# VM_Motor_v0t.net
KiCad netlist of a schematic drawn in EAGLE
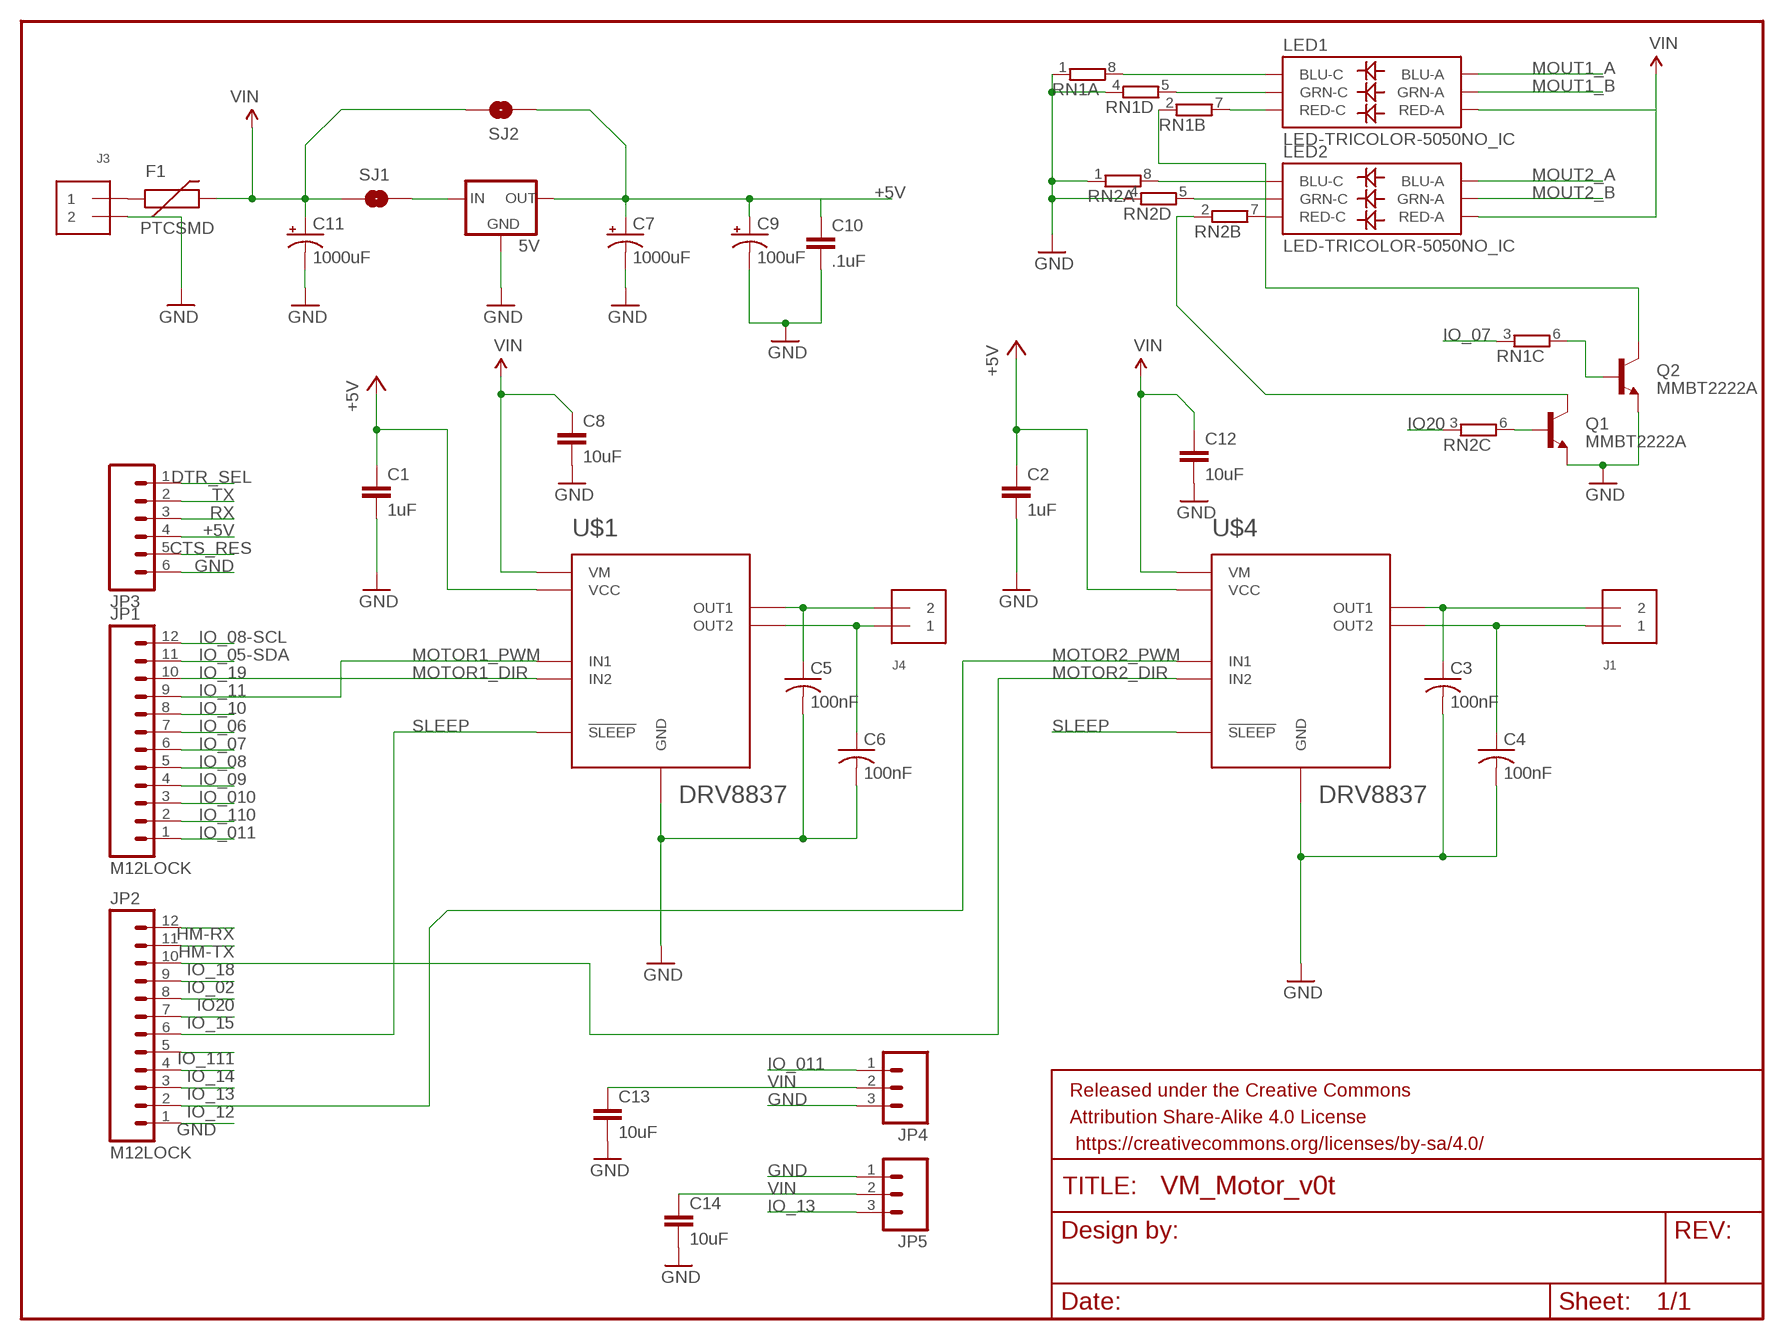
[diagram p0: schematic, sheet 1]

(export (version "E")
  (design (tool "Eeschema 10.0.6"))
  (components
    (comp (ref "5V")
      (value "V_REG_MC33269DT")
      (footprint "eagle-import:DPAK")
      (libsource (lib "eagle-import") (part "V_REG_MC33269DT"))
    )
    (comp (ref "C1")
      (value "1uF")
      (footprint "eagle-import:0402-CAP")
      (libsource (lib "eagle-import") (part "CAP0402-CAP"))
    )
    (comp (ref "C2")
      (value "1uF")
      (footprint "eagle-import:0402-CAP")
      (libsource (lib "eagle-import") (part "CAP0402-CAP"))
    )
    (comp (ref "C3")
      (value "100nF")
      (footprint "eagle-import:C0402")
      (libsource (lib "eagle-import") (part "C-USC0402"))
    )
    (comp (ref "C4")
      (value "100nF")
      (footprint "eagle-import:C0402")
      (libsource (lib "eagle-import") (part "C-USC0402"))
    )
    (comp (ref "C5")
      (value "100nF")
      (footprint "eagle-import:C0402")
      (libsource (lib "eagle-import") (part "C-USC0402"))
    )
    (comp (ref "C6")
      (value "100nF")
      (footprint "eagle-import:C0402")
      (libsource (lib "eagle-import") (part "C-USC0402"))
    )
    (comp (ref "C7")
      (value "1000uF")
      (footprint "eagle-import:140CLH-0810")
      (libsource (lib "eagle-import") (part "CPOL-US140CLH-0810"))
    )
    (comp (ref "C8")
      (value "10uF")
      (footprint "eagle-import:0402-CAP")
      (libsource (lib "eagle-import") (part "CAP0402-CAP"))
    )
    (comp (ref "C9")
      (value "100uF")
      (footprint "eagle-import:EIA3528-KIT")
      (libsource (lib "eagle-import") (part "CAP_POL3528-KIT"))
    )
    (comp (ref "C10")
      (value ".1uF")
      (footprint "eagle-import:0402-CAP")
      (libsource (lib "eagle-import") (part "CAP0402-CAP"))
    )
    (comp (ref "C11")
      (value "1000uF")
      (footprint "eagle-import:140CLH-0810")
      (libsource (lib "eagle-import") (part "CPOL-US140CLH-0810"))
    )
    (comp (ref "C12")
      (value "10uF")
      (footprint "eagle-import:0402-CAP")
      (libsource (lib "eagle-import") (part "CAP0402-CAP"))
    )
    (comp (ref "C13")
      (value "10uF")
      (footprint "eagle-import:0402-CAP")
      (libsource (lib "eagle-import") (part "CAP0402-CAP"))
    )
    (comp (ref "C14")
      (value "10uF")
      (footprint "eagle-import:0402-CAP")
      (libsource (lib "eagle-import") (part "CAP0402-CAP"))
    )
    (comp (ref "F1")
      (value "PTCSMD")
      (footprint "eagle-import:PTC-1206")
      (libsource (lib "eagle-import") (part "PTCSMD"))
    )
    (comp (ref "FRAME1")
      (value "FRAME-LETTER")
      (footprint "eagle-import:CREATIVE_COMMONS")
      (libsource (lib "eagle-import") (part "FRAME-LETTER"))
    )
    (comp (ref "J1")
      (value "TERMBLOCK_1X2")
      (footprint "eagle-import:TERMBLOCK_1X2-3.5MM")
      (libsource (lib "eagle-import") (part "TERMBLOCK_1X2"))
    )
    (comp (ref "J3")
      (value "TERMBLOCK_1X2")
      (footprint "eagle-import:TERMBLOCK_1X2-3.5MM")
      (libsource (lib "eagle-import") (part "TERMBLOCK_1X2"))
    )
    (comp (ref "J4")
      (value "TERMBLOCK_1X2")
      (footprint "eagle-import:TERMBLOCK_1X2-3.5MM")
      (libsource (lib "eagle-import") (part "TERMBLOCK_1X2"))
    )
    (comp (ref "JP1")
      (value "M12LOCK")
      (footprint "eagle-import:1X12_LOCK")
      (libsource (lib "eagle-import") (part "M12LOCK"))
    )
    (comp (ref "JP2")
      (value "M12LOCK")
      (footprint "eagle-import:1X12_LOCK")
      (libsource (lib "eagle-import") (part "M12LOCK"))
    )
    (comp (ref "JP3")
      (value "M06LOCK")
      (footprint "eagle-import:1X06_LOCK")
      (libsource (lib "eagle-import") (part "M06LOCK"))
    )
    (comp (ref "JP4")
      (value "M03LOCK")
      (footprint "eagle-import:1X03_LOCK")
      (libsource (lib "eagle-import") (part "M03LOCK"))
    )
    (comp (ref "JP5")
      (value "M03LOCK")
      (footprint "eagle-import:1X03_LOCK")
      (libsource (lib "eagle-import") (part "M03LOCK"))
    )
    (comp (ref "LED1")
      (value "LED-TRICOLOR-5050NO_IC")
      (footprint "eagle-import:LED-TRICOLOR-5050")
      (libsource (lib "eagle-import") (part "LED-TRICOLOR-5050NO_IC"))
    )
    (comp (ref "LED2")
      (value "LED-TRICOLOR-5050NO_IC")
      (footprint "eagle-import:LED-TRICOLOR-5050")
      (libsource (lib "eagle-import") (part "LED-TRICOLOR-5050NO_IC"))
    )
    (comp (ref "Q1")
      (value "MMBT2222A")
      (footprint "eagle-import:SOT23-3")
      (libsource (lib "eagle-import") (part "TRANSISTOR_NPNMMBT2222A"))
    )
    (comp (ref "Q2")
      (value "MMBT2222A")
      (footprint "eagle-import:SOT23-3")
      (libsource (lib "eagle-import") (part "TRANSISTOR_NPNMMBT2222A"))
    )
    (comp (ref "RN1")
      (value "4R-N0402ARV341")
      (footprint "eagle-import:4X0402ARV341")
      (libsource (lib "eagle-import") (part "4R-N0402ARV341"))
    )
    (comp (ref "RN2")
      (value "4R-N0402ARV341")
      (footprint "eagle-import:4X0402ARV341")
      (libsource (lib "eagle-import") (part "4R-N0402ARV341"))
    )
    (comp (ref "SJ1")
      (value "SOLDERJUMPERNO")
      (footprint "eagle-import:SJ_2S-NO")
      (libsource (lib "eagle-import") (part "SOLDERJUMPERNO"))
    )
    (comp (ref "SJ2")
      (value "SOLDERJUMPERNO")
      (footprint "eagle-import:SJ_2S-NO")
      (libsource (lib "eagle-import") (part "SOLDERJUMPERNO"))
    )
    (comp (ref "U$1")
      (value "DRV8837")
      (footprint "eagle-import:QFN8")
      (libsource (lib "eagle-import") (part "DRV8837"))
    )
    (comp (ref "U$4")
      (value "DRV8837")
      (footprint "eagle-import:QFN8")
      (libsource (lib "eagle-import") (part "DRV8837"))
    )
  )
  (nets
    (net (code "1") (name "+5V") (class "Default")
      (node (ref "5V") (pin "4") (pinfunction "OUT_4") (pintype "output"))
      (node (ref "C1") (pin "1") (pinfunction "1_1") (pintype "passive"))
      (node (ref "C10") (pin "1") (pinfunction "1_1") (pintype "passive"))
      (node (ref "C2") (pin "1") (pinfunction "1_1") (pintype "passive"))
      (node (ref "C7") (pin "+") (pinfunction "+_+") (pintype "passive"))
      (node (ref "C9") (pin "A") (pinfunction "+_A") (pintype "passive"))
      (node (ref "JP3") (pin "4") (pinfunction "4_4") (pintype "passive"))
      (node (ref "SJ2") (pin "1") (pinfunction "1_1") (pintype "passive"))
      (node (ref "U$1") (pin "P$8") (pinfunction "VCC_P$8") (pintype "bidirectional"))
      (node (ref "U$4") (pin "P$8") (pinfunction "VCC_P$8") (pintype "bidirectional"))
    )
    (net (code "2") (name "/CTS_RES") (class "Default")
      (node (ref "JP3") (pin "5") (pinfunction "5_5") (pintype "passive"))
    )
    (net (code "3") (name "/DTR_SEL") (class "Default")
      (node (ref "JP3") (pin "1") (pinfunction "1_1") (pintype "passive"))
    )
    (net (code "4") (name "/HM-RX") (class "Default")
      (node (ref "JP2") (pin "12") (pinfunction "12_12") (pintype "passive"))
    )
    (net (code "5") (name "/HM-TX") (class "Default")
      (node (ref "JP2") (pin "11") (pinfunction "11_11") (pintype "passive"))
    )
    (net (code "6") (name "/IO20") (class "Default")
      (node (ref "JP2") (pin "8") (pinfunction "8_8") (pintype "passive"))
      (node (ref "RN2") (pin "3") (pinfunction "1_3") (pintype "passive"))
    )
    (net (code "7") (name "/IO_02") (class "Default")
      (node (ref "JP2") (pin "9") (pinfunction "9_9") (pintype "passive"))
    )
    (net (code "8") (name "/IO_05-SDA") (class "Default")
      (node (ref "JP1") (pin "11") (pinfunction "11_11") (pintype "passive"))
    )
    (net (code "9") (name "/IO_06") (class "Default")
      (node (ref "JP1") (pin "7") (pinfunction "7_7") (pintype "passive"))
    )
    (net (code "10") (name "/IO_07") (class "Default")
      (node (ref "JP1") (pin "6") (pinfunction "6_6") (pintype "passive"))
      (node (ref "RN1") (pin "3") (pinfunction "1_3") (pintype "passive"))
    )
    (net (code "11") (name "/IO_08") (class "Default")
      (node (ref "JP1") (pin "5") (pinfunction "5_5") (pintype "passive"))
    )
    (net (code "12") (name "/IO_08-SCL") (class "Default")
      (node (ref "JP1") (pin "12") (pinfunction "12_12") (pintype "passive"))
    )
    (net (code "13") (name "/IO_09") (class "Default")
      (node (ref "JP1") (pin "4") (pinfunction "4_4") (pintype "passive"))
    )
    (net (code "14") (name "/IO_10") (class "Default")
      (node (ref "JP1") (pin "8") (pinfunction "8_8") (pintype "passive"))
    )
    (net (code "15") (name "/IO_010") (class "Default")
      (node (ref "JP1") (pin "3") (pinfunction "3_3") (pintype "passive"))
    )
    (net (code "16") (name "/IO_011") (class "Default")
      (node (ref "JP1") (pin "1") (pinfunction "1_1") (pintype "passive"))
      (node (ref "JP4") (pin "1") (pinfunction "1_1") (pintype "passive"))
    )
    (net (code "17") (name "/IO_13") (class "Default")
      (node (ref "JP2") (pin "3") (pinfunction "3_3") (pintype "passive"))
      (node (ref "JP5") (pin "3") (pinfunction "3_3") (pintype "passive"))
    )
    (net (code "18") (name "/IO_14") (class "Default")
      (node (ref "JP2") (pin "4") (pinfunction "4_4") (pintype "passive"))
    )
    (net (code "19") (name "/IO_15") (class "Default")
      (node (ref "JP2") (pin "7") (pinfunction "7_7") (pintype "passive"))
    )
    (net (code "20") (name "/IO_110") (class "Default")
      (node (ref "JP1") (pin "2") (pinfunction "2_2") (pintype "passive"))
    )
    (net (code "21") (name "/IO_111") (class "Default")
      (node (ref "JP2") (pin "5") (pinfunction "5_5") (pintype "passive"))
    )
    (net (code "22") (name "/MOTOR1_DIR") (class "Default")
      (node (ref "JP1") (pin "10") (pinfunction "10_10") (pintype "passive"))
      (node (ref "U$1") (pin "P$5") (pinfunction "IN2_P$5") (pintype "bidirectional"))
    )
    (net (code "23") (name "/MOTOR1_PWM") (class "Default")
      (node (ref "JP1") (pin "9") (pinfunction "9_9") (pintype "passive"))
      (node (ref "U$1") (pin "P$6") (pinfunction "IN1_P$6") (pintype "bidirectional"))
    )
    (net (code "24") (name "/MOTOR2_DIR") (class "Default")
      (node (ref "JP2") (pin "10") (pinfunction "10_10") (pintype "passive"))
      (node (ref "U$4") (pin "P$5") (pinfunction "IN2_P$5") (pintype "bidirectional"))
    )
    (net (code "25") (name "/MOTOR2_PWM") (class "Default")
      (node (ref "JP2") (pin "2") (pinfunction "2_2") (pintype "passive"))
      (node (ref "U$4") (pin "P$6") (pinfunction "IN1_P$6") (pintype "bidirectional"))
    )
    (net (code "26") (name "/MOUT1_A") (class "Default")
      (node (ref "C5") (pin "1") (pinfunction "1_1") (pintype "passive"))
      (node (ref "J4") (pin "2") (pinfunction "2_2") (pintype "passive"))
      (node (ref "LED1") (pin "3") (pinfunction "BLU-A_3") (pintype "bidirectional"))
      (node (ref "U$1") (pin "P$2") (pinfunction "OUT1_P$2") (pintype "bidirectional"))
    )
    (net (code "27") (name "/MOUT1_B") (class "Default")
      (node (ref "C6") (pin "1") (pinfunction "1_1") (pintype "passive"))
      (node (ref "J4") (pin "1") (pinfunction "1_1") (pintype "passive"))
      (node (ref "LED1") (pin "1") (pinfunction "GRN-A_1") (pintype "bidirectional"))
      (node (ref "U$1") (pin "P$3") (pinfunction "OUT2_P$3") (pintype "bidirectional"))
    )
    (net (code "28") (name "/MOUT2_A") (class "Default")
      (node (ref "C3") (pin "1") (pinfunction "1_1") (pintype "passive"))
      (node (ref "J1") (pin "2") (pinfunction "2_2") (pintype "passive"))
      (node (ref "LED2") (pin "3") (pinfunction "BLU-A_3") (pintype "bidirectional"))
      (node (ref "U$4") (pin "P$2") (pinfunction "OUT1_P$2") (pintype "bidirectional"))
    )
    (net (code "29") (name "/MOUT2_B") (class "Default")
      (node (ref "C4") (pin "1") (pinfunction "1_1") (pintype "passive"))
      (node (ref "J1") (pin "1") (pinfunction "1_1") (pintype "passive"))
      (node (ref "LED2") (pin "1") (pinfunction "GRN-A_1") (pintype "bidirectional"))
      (node (ref "U$4") (pin "P$3") (pinfunction "OUT2_P$3") (pintype "bidirectional"))
    )
    (net (code "30") (name "/RX") (class "Default")
      (node (ref "JP3") (pin "3") (pinfunction "3_3") (pintype "passive"))
    )
    (net (code "31") (name "/SLEEP") (class "Default")
      (node (ref "JP2") (pin "6") (pinfunction "6_6") (pintype "passive"))
      (node (ref "U$1") (pin "P$7") (pinfunction "~{SLEEP}_P$7") (pintype "bidirectional"))
      (node (ref "U$4") (pin "P$7") (pinfunction "~{SLEEP}_P$7") (pintype "bidirectional"))
    )
    (net (code "32") (name "/TX") (class "Default")
      (node (ref "JP3") (pin "2") (pinfunction "2_2") (pintype "passive"))
    )
    (net (code "33") (name "GND") (class "Default")
      (node (ref "5V") (pin "1") (pinfunction "GND_1") (pintype "input"))
      (node (ref "C1") (pin "2") (pinfunction "2_2") (pintype "passive"))
      (node (ref "C10") (pin "2") (pinfunction "2_2") (pintype "passive"))
      (node (ref "C11") (pin "-") (pinfunction "-_-") (pintype "passive"))
      (node (ref "C12") (pin "2") (pinfunction "2_2") (pintype "passive"))
      (node (ref "C13") (pin "2") (pinfunction "2_2") (pintype "passive"))
      (node (ref "C14") (pin "2") (pinfunction "2_2") (pintype "passive"))
      (node (ref "C2") (pin "2") (pinfunction "2_2") (pintype "passive"))
      (node (ref "C3") (pin "2") (pinfunction "2_2") (pintype "passive"))
      (node (ref "C4") (pin "2") (pinfunction "2_2") (pintype "passive"))
      (node (ref "C5") (pin "2") (pinfunction "2_2") (pintype "passive"))
      (node (ref "C6") (pin "2") (pinfunction "2_2") (pintype "passive"))
      (node (ref "C7") (pin "-") (pinfunction "-_-") (pintype "passive"))
      (node (ref "C8") (pin "2") (pinfunction "2_2") (pintype "passive"))
      (node (ref "C9") (pin "C") (pinfunction "-_C") (pintype "passive"))
      (node (ref "J3") (pin "2") (pinfunction "2_2") (pintype "passive"))
      (node (ref "JP2") (pin "1") (pinfunction "1_1") (pintype "passive"))
      (node (ref "JP3") (pin "6") (pinfunction "6_6") (pintype "passive"))
      (node (ref "JP4") (pin "3") (pinfunction "3_3") (pintype "passive"))
      (node (ref "JP5") (pin "1") (pinfunction "1_1") (pintype "passive"))
      (node (ref "Q1") (pin "2") (pinfunction "E_2") (pintype "passive"))
      (node (ref "Q2") (pin "2") (pinfunction "E_2") (pintype "passive"))
      (node (ref "RN1") (pin "1") (pinfunction "1_1") (pintype "passive"))
      (node (ref "RN1") (pin "4") (pinfunction "1_4") (pintype "passive"))
      (node (ref "RN2") (pin "1") (pinfunction "1_1") (pintype "passive"))
      (node (ref "RN2") (pin "4") (pinfunction "1_4") (pintype "passive"))
      (node (ref "U$1") (pin "P$10") (pinfunction "GND_P$10") (pintype "bidirectional"))
      (node (ref "U$1") (pin "P$11") (pinfunction "GND_P$11") (pintype "bidirectional"))
      (node (ref "U$1") (pin "P$4") (pinfunction "GND_P$4") (pintype "bidirectional"))
      (node (ref "U$1") (pin "P$9") (pinfunction "GND_P$9") (pintype "bidirectional"))
      (node (ref "U$4") (pin "P$10") (pinfunction "GND_P$10") (pintype "bidirectional"))
      (node (ref "U$4") (pin "P$11") (pinfunction "GND_P$11") (pintype "bidirectional"))
      (node (ref "U$4") (pin "P$4") (pinfunction "GND_P$4") (pintype "bidirectional"))
      (node (ref "U$4") (pin "P$9") (pinfunction "GND_P$9") (pintype "bidirectional"))
    )
    (net (code "34") (name "Net-(5V-IN)") (class "Default")
      (node (ref "5V") (pin "3") (pinfunction "IN_3") (pintype "input"))
      (node (ref "SJ1") (pin "2") (pinfunction "2_2") (pintype "passive"))
    )
    (net (code "35") (name "Net-(F1-Pad1)") (class "Default")
      (node (ref "F1") (pin "1") (pinfunction "1_1") (pintype "bidirectional"))
      (node (ref "J3") (pin "1") (pinfunction "1_1") (pintype "passive"))
    )
    (net (code "36") (name "Net-(LED1-BLU-C)") (class "Default")
      (node (ref "LED1") (pin "4") (pinfunction "BLU-C_4") (pintype "bidirectional"))
      (node (ref "RN1") (pin "8") (pinfunction "2_8") (pintype "passive"))
    )
    (net (code "37") (name "Net-(LED1-GRN-C)") (class "Default")
      (node (ref "LED1") (pin "6") (pinfunction "GRN-C_6") (pintype "bidirectional"))
      (node (ref "RN1") (pin "5") (pinfunction "2_5") (pintype "passive"))
    )
    (net (code "38") (name "Net-(LED1-RED-C)") (class "Default")
      (node (ref "LED1") (pin "5") (pinfunction "RED-C_5") (pintype "bidirectional"))
      (node (ref "RN1") (pin "7") (pinfunction "2_7") (pintype "passive"))
    )
    (net (code "39") (name "Net-(LED2-BLU-C)") (class "Default")
      (node (ref "LED2") (pin "4") (pinfunction "BLU-C_4") (pintype "bidirectional"))
      (node (ref "RN2") (pin "8") (pinfunction "2_8") (pintype "passive"))
    )
    (net (code "40") (name "Net-(LED2-GRN-C)") (class "Default")
      (node (ref "LED2") (pin "6") (pinfunction "GRN-C_6") (pintype "bidirectional"))
      (node (ref "RN2") (pin "5") (pinfunction "2_5") (pintype "passive"))
    )
    (net (code "41") (name "Net-(LED2-RED-C)") (class "Default")
      (node (ref "LED2") (pin "5") (pinfunction "RED-C_5") (pintype "bidirectional"))
      (node (ref "RN2") (pin "7") (pinfunction "2_7") (pintype "passive"))
    )
    (net (code "42") (name "Net-(Q1-B)") (class "Default")
      (node (ref "Q1") (pin "1") (pinfunction "B_1") (pintype "passive"))
      (node (ref "RN2") (pin "6") (pinfunction "2_6") (pintype "passive"))
    )
    (net (code "43") (name "Net-(Q1-C)") (class "Default")
      (node (ref "Q1") (pin "3") (pinfunction "C_3") (pintype "passive"))
      (node (ref "RN2") (pin "2") (pinfunction "1_2") (pintype "passive"))
    )
    (net (code "44") (name "Net-(Q2-B)") (class "Default")
      (node (ref "Q2") (pin "1") (pinfunction "B_1") (pintype "passive"))
      (node (ref "RN1") (pin "6") (pinfunction "2_6") (pintype "passive"))
    )
    (net (code "45") (name "Net-(Q2-C)") (class "Default")
      (node (ref "Q2") (pin "3") (pinfunction "C_3") (pintype "passive"))
      (node (ref "RN1") (pin "2") (pinfunction "1_2") (pintype "passive"))
    )
    (net (code "46") (name "VIN") (class "Default")
      (node (ref "C11") (pin "+") (pinfunction "+_+") (pintype "passive"))
      (node (ref "C12") (pin "1") (pinfunction "1_1") (pintype "passive"))
      (node (ref "C13") (pin "1") (pinfunction "1_1") (pintype "passive"))
      (node (ref "C14") (pin "1") (pinfunction "1_1") (pintype "passive"))
      (node (ref "C8") (pin "1") (pinfunction "1_1") (pintype "passive"))
      (node (ref "F1") (pin "2") (pinfunction "2_2") (pintype "bidirectional"))
      (node (ref "JP4") (pin "2") (pinfunction "2_2") (pintype "passive"))
      (node (ref "JP5") (pin "2") (pinfunction "2_2") (pintype "passive"))
      (node (ref "LED1") (pin "2") (pinfunction "RED-A_2") (pintype "bidirectional"))
      (node (ref "LED2") (pin "2") (pinfunction "RED-A_2") (pintype "bidirectional"))
      (node (ref "SJ1") (pin "1") (pinfunction "1_1") (pintype "passive"))
      (node (ref "SJ2") (pin "2") (pinfunction "2_2") (pintype "passive"))
      (node (ref "U$1") (pin "P$1") (pinfunction "VM_P$1") (pintype "bidirectional"))
      (node (ref "U$4") (pin "P$1") (pinfunction "VM_P$1") (pintype "bidirectional"))
    )
  )
)
